# MotorController.net
KiCad netlist of a schematic drawn in EAGLE
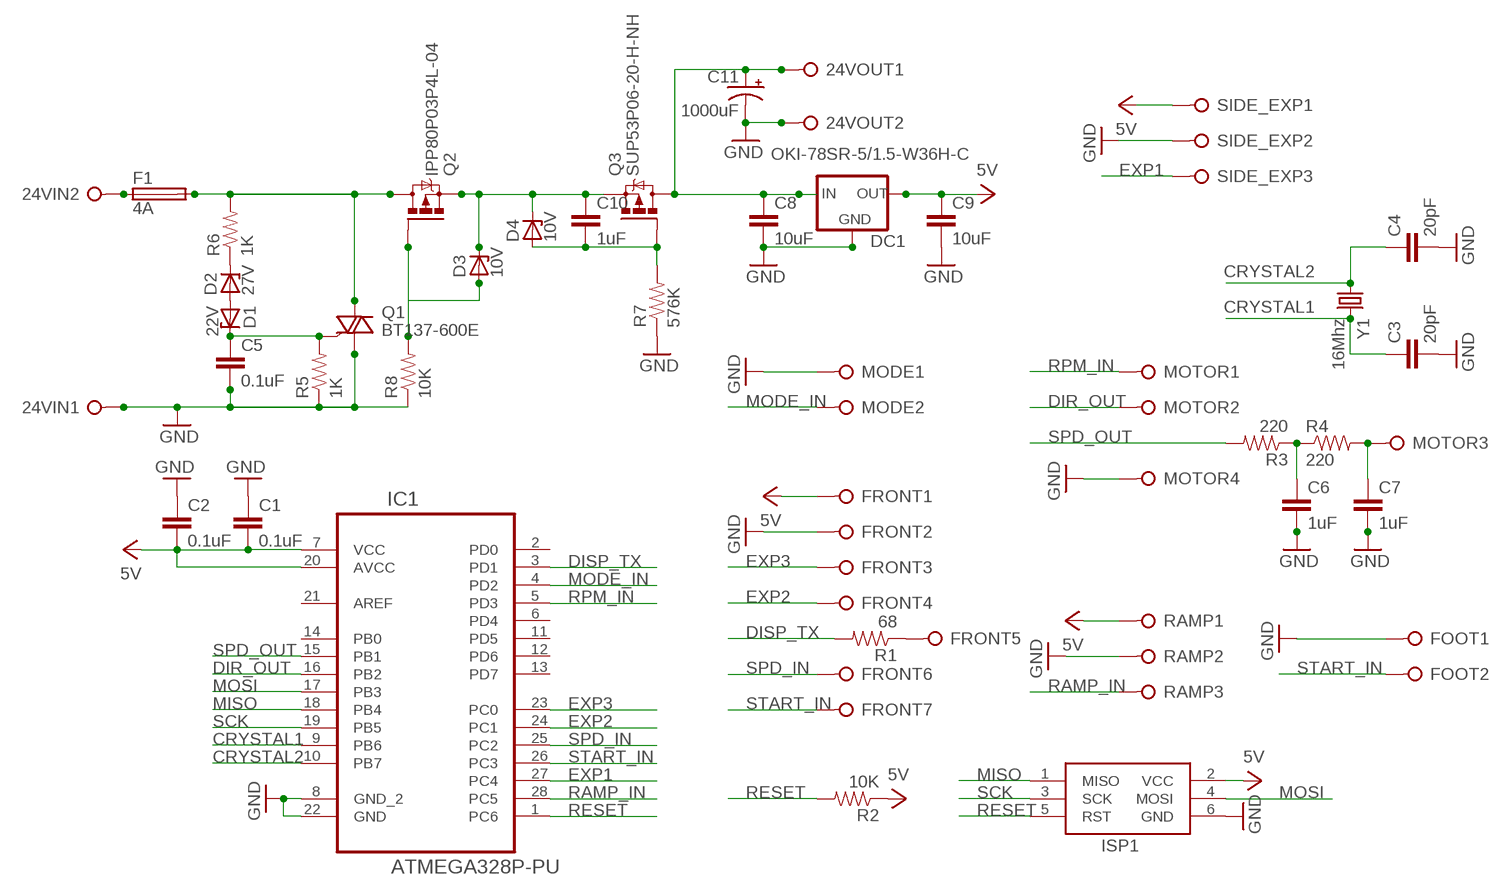
[diagram p0: schematic, sheet 1]

(export (version "E")
  (design (tool "Eeschema 10.0.6"))
  (components
    (comp (ref "24VIN")
      (value "PINHD-1X2BIG")
      (footprint "eagle-import:1X02-BIG")
      (libsource (lib "eagle-import") (part "PINHD-1X2BIG"))
    )
    (comp (ref "24VOUT")
      (value "PINHD-1X2BIG")
      (footprint "eagle-import:1X02-BIG")
      (libsource (lib "eagle-import") (part "PINHD-1X2BIG"))
    )
    (comp (ref "C1")
      (value "0.1uF")
      (footprint "eagle-import:CAPACITOR-2.5MM")
      (libsource (lib "eagle-import") (part "CAPACITOR-2.5MM"))
    )
    (comp (ref "C2")
      (value "0.1uF")
      (footprint "eagle-import:CAPACITOR-2.5MM")
      (libsource (lib "eagle-import") (part "CAPACITOR-2.5MM"))
    )
    (comp (ref "C3")
      (value "20pF")
      (footprint "eagle-import:CAPACITOR-2.5MM")
      (libsource (lib "eagle-import") (part "CAPACITOR-2.5MM"))
    )
    (comp (ref "C4")
      (value "20pF")
      (footprint "eagle-import:CAPACITOR-2.5MM")
      (libsource (lib "eagle-import") (part "CAPACITOR-2.5MM"))
    )
    (comp (ref "C5")
      (value "0.1uF")
      (footprint "eagle-import:CAPACITOR-2.5MM")
      (libsource (lib "eagle-import") (part "CAPACITOR-2.5MM"))
    )
    (comp (ref "C6")
      (value "1uF")
      (footprint "eagle-import:CAPACITOR-2.5MM")
      (libsource (lib "eagle-import") (part "CAPACITOR-2.5MM"))
    )
    (comp (ref "C7")
      (value "1uF")
      (footprint "eagle-import:CAPACITOR-2.5MM")
      (libsource (lib "eagle-import") (part "CAPACITOR-2.5MM"))
    )
    (comp (ref "C8")
      (value "10uF")
      (footprint "eagle-import:CAPACITOR-5MM")
      (libsource (lib "eagle-import") (part "CAPACITOR-5MM"))
    )
    (comp (ref "C9")
      (value "10uF")
      (footprint "eagle-import:CAPACITOR-5MM")
      (libsource (lib "eagle-import") (part "CAPACITOR-5MM"))
    )
    (comp (ref "C10")
      (value "1uF")
      (footprint "eagle-import:CAPACITOR-2.5MM")
      (libsource (lib "eagle-import") (part "CAPACITOR-2.5MM"))
    )
    (comp (ref "C11")
      (value "1000uF")
      (footprint "eagle-import:CAP-POL-25-14")
      (libsource (lib "eagle-import") (part "CAP-POL-25-14"))
    )
    (comp (ref "D1")
      (value "22V")
      (footprint "eagle-import:ZDIO-7.5")
      (libsource (lib "eagle-import") (part "ZENER-7.5"))
    )
    (comp (ref "D2")
      (value "27V")
      (footprint "eagle-import:ZDIO-7.5")
      (libsource (lib "eagle-import") (part "ZENER-7.5"))
    )
    (comp (ref "D3")
      (value "10V")
      (footprint "eagle-import:ZDIO-7.5")
      (libsource (lib "eagle-import") (part "ZENER-7.5"))
    )
    (comp (ref "D4")
      (value "10V")
      (footprint "eagle-import:ZDIO-7.5")
      (libsource (lib "eagle-import") (part "ZENER-7.5"))
    )
    (comp (ref "DC1")
      (value "OKI-78SR-5/1.5-W36H-C")
      (footprint "eagle-import:DC-CONV")
      (libsource (lib "eagle-import") (part "DC-CONV"))
    )
    (comp (ref "F1")
      (value "4A")
      (footprint "eagle-import:FUSE_HOLDER_5X20MM")
      (libsource (lib "eagle-import") (part "FUSE"))
    )
    (comp (ref "FOOT")
      (value "PINHD-1X2BIG")
      (footprint "eagle-import:1X02-BIG")
      (libsource (lib "eagle-import") (part "PINHD-1X2BIG"))
    )
    (comp (ref "FRONT")
      (value "PINHD-1X7BIG")
      (footprint "eagle-import:1X07-BIG")
      (libsource (lib "eagle-import") (part "PINHD-1X7BIG"))
    )
    (comp (ref "IC1")
      (value "ATMEGA328P-PU")
      (footprint "eagle-import:DIP28")
      (libsource (lib "eagle-import") (part "ATMEGA328P-PU"))
    )
    (comp (ref "ISP1")
      (value "ICSP-HEADER-6")
      (footprint "eagle-import:ICSP-HEADER")
      (libsource (lib "eagle-import") (part "ICSP-HEADER-6"))
    )
    (comp (ref "MODE")
      (value "PINHD-1X2BIG")
      (footprint "eagle-import:1X02-BIG")
      (libsource (lib "eagle-import") (part "PINHD-1X2BIG"))
    )
    (comp (ref "MOTOR")
      (value "PINHD-1X4BIG")
      (footprint "eagle-import:1X04-BIG")
      (libsource (lib "eagle-import") (part "PINHD-1X4BIG"))
    )
    (comp (ref "Q1")
      (value "BT137-600E")
      (footprint "eagle-import:TO220BH-NO-HOLE")
      (libsource (lib "eagle-import") (part "TRIAC-H-NH"))
    )
    (comp (ref "Q2")
      (value "IPP80P03P4L-04")
      (footprint "eagle-import:TO220BH-NO-HOLE")
      (libsource (lib "eagle-import") (part "SUP53P06-20-H-NH"))
    )
    (comp (ref "Q3")
      (value "SUP53P06-20-H-NH")
      (footprint "eagle-import:TO220BH-NO-HOLE")
      (libsource (lib "eagle-import") (part "SUP53P06-20-H-NH"))
    )
    (comp (ref "R1")
      (value "68")
      (footprint "eagle-import:AXIAL-7.5MM")
      (libsource (lib "eagle-import") (part "RESISTOR-7.5MM"))
    )
    (comp (ref "R2")
      (value "10K")
      (footprint "eagle-import:AXIAL-7.5MM")
      (libsource (lib "eagle-import") (part "RESISTOR-7.5MM"))
    )
    (comp (ref "R3")
      (value "220")
      (footprint "eagle-import:AXIAL-7.5MM")
      (libsource (lib "eagle-import") (part "RESISTOR-7.5MM"))
    )
    (comp (ref "R4")
      (value "220")
      (footprint "eagle-import:AXIAL-7.5MM")
      (libsource (lib "eagle-import") (part "RESISTOR-7.5MM"))
    )
    (comp (ref "R5")
      (value "1K")
      (footprint "eagle-import:AXIAL-7.5MM")
      (libsource (lib "eagle-import") (part "RESISTOR-7.5MM"))
    )
    (comp (ref "R6")
      (value "1K")
      (footprint "eagle-import:AXIAL-7.5MM")
      (libsource (lib "eagle-import") (part "RESISTOR-7.5MM"))
    )
    (comp (ref "R7")
      (value "576K")
      (footprint "eagle-import:AXIAL-7.5MM")
      (libsource (lib "eagle-import") (part "RESISTOR-7.5MM"))
    )
    (comp (ref "R8")
      (value "10K")
      (footprint "eagle-import:AXIAL-7.5MM")
      (libsource (lib "eagle-import") (part "RESISTOR-7.5MM"))
    )
    (comp (ref "RAMP")
      (value "PINHD-1X3BIG")
      (footprint "eagle-import:1X03-BIG")
      (libsource (lib "eagle-import") (part "PINHD-1X3BIG"))
    )
    (comp (ref "SIDE_EXP")
      (value "PINHD-1X3BIG")
      (footprint "eagle-import:1X03-BIG")
      (libsource (lib "eagle-import") (part "PINHD-1X3BIG"))
    )
    (comp (ref "Y1")
      (value "16Mhz")
      (footprint "eagle-import:CRYSTAL-V")
      (libsource (lib "eagle-import") (part "CRYSTAL-V"))
    )
  )
  (nets
    (net (code "1") (name "/CRYSTAL1") (class "Default")
      (node (ref "C3") (pin "1") (pinfunction "1_1") (pintype "passive"))
      (node (ref "IC1") (pin "9") (pinfunction "PB6_9") (pintype "bidirectional"))
      (node (ref "Y1") (pin "2") (pinfunction "2_2") (pintype "passive"))
    )
    (net (code "2") (name "/CRYSTAL2") (class "Default")
      (node (ref "C4") (pin "1") (pinfunction "1_1") (pintype "passive"))
      (node (ref "IC1") (pin "10") (pinfunction "PB7_10") (pintype "bidirectional"))
      (node (ref "Y1") (pin "1") (pinfunction "1_1") (pintype "passive"))
    )
    (net (code "3") (name "/DIR_OUT") (class "Default")
      (node (ref "IC1") (pin "16") (pinfunction "PB2_16") (pintype "bidirectional"))
      (node (ref "MOTOR") (pin "2") (pinfunction "KL_2") (pintype "passive"))
    )
    (net (code "4") (name "/DISP_TX") (class "Default")
      (node (ref "IC1") (pin "3") (pinfunction "PD1_3") (pintype "bidirectional"))
      (node (ref "R1") (pin "P$2") (pinfunction "2_P$2") (pintype "passive"))
    )
    (net (code "5") (name "/EXP1") (class "Default")
      (node (ref "IC1") (pin "27") (pinfunction "PC4_27") (pintype "bidirectional"))
      (node (ref "SIDE_EXP") (pin "3") (pinfunction "KL_3") (pintype "passive"))
    )
    (net (code "6") (name "/EXP2") (class "Default")
      (node (ref "FRONT") (pin "4") (pinfunction "KL_4") (pintype "passive"))
      (node (ref "IC1") (pin "24") (pinfunction "PC1_24") (pintype "bidirectional"))
    )
    (net (code "7") (name "/EXP3") (class "Default")
      (node (ref "FRONT") (pin "3") (pinfunction "KL_3") (pintype "passive"))
      (node (ref "IC1") (pin "23") (pinfunction "PC0_23") (pintype "bidirectional"))
    )
    (net (code "8") (name "/MISO") (class "Default")
      (node (ref "IC1") (pin "18") (pinfunction "PB4_18") (pintype "bidirectional"))
      (node (ref "ISP1") (pin "1") (pinfunction "MISO_1") (pintype "input"))
    )
    (net (code "9") (name "/MODE_IN") (class "Default")
      (node (ref "IC1") (pin "4") (pinfunction "PD2_4") (pintype "bidirectional"))
      (node (ref "MODE") (pin "2") (pinfunction "KL_2") (pintype "passive"))
    )
    (net (code "10") (name "/MOSI") (class "Default")
      (node (ref "IC1") (pin "17") (pinfunction "PB3_17") (pintype "bidirectional"))
      (node (ref "ISP1") (pin "4") (pinfunction "MOSI_4") (pintype "output"))
    )
    (net (code "11") (name "/RAMP_IN") (class "Default")
      (node (ref "IC1") (pin "28") (pinfunction "PC5_28") (pintype "bidirectional"))
      (node (ref "RAMP") (pin "3") (pinfunction "KL_3") (pintype "passive"))
    )
    (net (code "12") (name "/RESET") (class "Default")
      (node (ref "IC1") (pin "1") (pinfunction "PC6_1") (pintype "bidirectional"))
      (node (ref "ISP1") (pin "5") (pinfunction "RST_5") (pintype "output"))
      (node (ref "R2") (pin "P$2") (pinfunction "2_P$2") (pintype "passive"))
    )
    (net (code "13") (name "/RPM_IN") (class "Default")
      (node (ref "IC1") (pin "5") (pinfunction "PD3_5") (pintype "bidirectional"))
      (node (ref "MOTOR") (pin "1") (pinfunction "KL_1") (pintype "passive"))
    )
    (net (code "14") (name "/SCK") (class "Default")
      (node (ref "IC1") (pin "19") (pinfunction "PB5_19") (pintype "bidirectional"))
      (node (ref "ISP1") (pin "3") (pinfunction "SCK_3") (pintype "output"))
    )
    (net (code "15") (name "/SPD_IN") (class "Default")
      (node (ref "FRONT") (pin "6") (pinfunction "KL_6") (pintype "passive"))
      (node (ref "IC1") (pin "25") (pinfunction "PC2_25") (pintype "bidirectional"))
    )
    (net (code "16") (name "/SPD_OUT") (class "Default")
      (node (ref "IC1") (pin "15") (pinfunction "PB1_15") (pintype "bidirectional"))
      (node (ref "R3") (pin "P$2") (pinfunction "2_P$2") (pintype "passive"))
    )
    (net (code "17") (name "/START_IN") (class "Default")
      (node (ref "FOOT") (pin "2") (pinfunction "KL_2") (pintype "passive"))
      (node (ref "FRONT") (pin "7") (pinfunction "KL_7") (pintype "passive"))
      (node (ref "IC1") (pin "26") (pinfunction "PC3_26") (pintype "bidirectional"))
    )
    (net (code "18") (name "5V") (class "Default")
      (node (ref "C1") (pin "2") (pinfunction "2_2") (pintype "passive"))
      (node (ref "C2") (pin "2") (pinfunction "2_2") (pintype "passive"))
      (node (ref "C9") (pin "1") (pinfunction "1_1") (pintype "passive"))
      (node (ref "DC1") (pin "P3") (pinfunction "OUT_P3") (pintype "passive"))
      (node (ref "FRONT") (pin "1") (pinfunction "KL_1") (pintype "passive"))
      (node (ref "IC1") (pin "20") (pinfunction "AVCC_20") (pintype "power_in"))
      (node (ref "IC1") (pin "7") (pinfunction "VCC_7") (pintype "power_in"))
      (node (ref "ISP1") (pin "2") (pinfunction "VCC_2") (pintype "power_in"))
      (node (ref "R2") (pin "P$1") (pinfunction "1_P$1") (pintype "passive"))
      (node (ref "RAMP") (pin "1") (pinfunction "KL_1") (pintype "passive"))
      (node (ref "SIDE_EXP") (pin "1") (pinfunction "KL_1") (pintype "passive"))
    )
    (net (code "19") (name "GND") (class "Default")
      (node (ref "24VIN") (pin "1") (pinfunction "KL_1") (pintype "passive"))
      (node (ref "24VOUT") (pin "2") (pinfunction "KL_2") (pintype "passive"))
      (node (ref "C1") (pin "1") (pinfunction "1_1") (pintype "passive"))
      (node (ref "C11") (pin "-") (pinfunction "-_-") (pintype "passive"))
      (node (ref "C2") (pin "1") (pinfunction "1_1") (pintype "passive"))
      (node (ref "C3") (pin "2") (pinfunction "2_2") (pintype "passive"))
      (node (ref "C4") (pin "2") (pinfunction "2_2") (pintype "passive"))
      (node (ref "C5") (pin "2") (pinfunction "2_2") (pintype "passive"))
      (node (ref "C6") (pin "2") (pinfunction "2_2") (pintype "passive"))
      (node (ref "C7") (pin "2") (pinfunction "2_2") (pintype "passive"))
      (node (ref "C8") (pin "2") (pinfunction "2_2") (pintype "passive"))
      (node (ref "C9") (pin "2") (pinfunction "2_2") (pintype "passive"))
      (node (ref "DC1") (pin "P2") (pinfunction "GND_P2") (pintype "input"))
      (node (ref "FOOT") (pin "1") (pinfunction "KL_1") (pintype "passive"))
      (node (ref "FRONT") (pin "2") (pinfunction "KL_2") (pintype "passive"))
      (node (ref "IC1") (pin "22") (pinfunction "GND_22") (pintype "passive"))
      (node (ref "IC1") (pin "8") (pinfunction "GND_2_8") (pintype "passive"))
      (node (ref "ISP1") (pin "6") (pinfunction "GND_6") (pintype "power_in"))
      (node (ref "MODE") (pin "1") (pinfunction "KL_1") (pintype "passive"))
      (node (ref "MOTOR") (pin "4") (pinfunction "KL_4") (pintype "passive"))
      (node (ref "Q1") (pin "P1") (pinfunction "A1_P1") (pintype "passive"))
      (node (ref "R5") (pin "P$1") (pinfunction "1_P$1") (pintype "passive"))
      (node (ref "R7") (pin "P$1") (pinfunction "1_P$1") (pintype "passive"))
      (node (ref "R8") (pin "P$1") (pinfunction "1_P$1") (pintype "passive"))
      (node (ref "RAMP") (pin "2") (pinfunction "KL_2") (pintype "passive"))
      (node (ref "SIDE_EXP") (pin "2") (pinfunction "KL_2") (pintype "passive"))
    )
    (net (code "20") (name "Net-(24VINB-KL)") (class "Default")
      (node (ref "24VIN") (pin "2") (pinfunction "KL_2") (pintype "passive"))
      (node (ref "F1") (pin "1") (pinfunction "1_1") (pintype "passive"))
    )
    (net (code "21") (name "Net-(24VOUTA-KL)") (class "Default")
      (node (ref "24VOUT") (pin "1") (pinfunction "KL_1") (pintype "passive"))
      (node (ref "C11") (pin "+") (pinfunction "+_+") (pintype "passive"))
      (node (ref "C8") (pin "1") (pinfunction "1_1") (pintype "passive"))
      (node (ref "DC1") (pin "P1") (pinfunction "IN_P1") (pintype "input"))
      (node (ref "Q3") (pin "P2") (pinfunction "D_P2") (pintype "passive"))
    )
    (net (code "22") (name "Net-(D1-PadA)") (class "Default")
      (node (ref "D1") (pin "A") (pinfunction "A_A") (pintype "passive"))
      (node (ref "D2") (pin "A") (pinfunction "A_A") (pintype "passive"))
    )
    (net (code "23") (name "Net-(FRONTE-KL)") (class "Default")
      (node (ref "FRONT") (pin "5") (pinfunction "KL_5") (pintype "passive"))
      (node (ref "R1") (pin "P$1") (pinfunction "1_P$1") (pintype "passive"))
    )
    (net (code "24") (name "Net-(MOTORC-KL)") (class "Default")
      (node (ref "C7") (pin "1") (pinfunction "1_1") (pintype "passive"))
      (node (ref "MOTOR") (pin "3") (pinfunction "KL_3") (pintype "passive"))
      (node (ref "R4") (pin "P$2") (pinfunction "2_P$2") (pintype "passive"))
    )
    (net (code "25") (name "Net-(Q1-A2)") (class "Default")
      (node (ref "F1") (pin "2") (pinfunction "2_2") (pintype "passive"))
      (node (ref "Q1") (pin "P2") (pinfunction "A2_P2") (pintype "passive"))
      (node (ref "Q2") (pin "P2") (pinfunction "D_P2") (pintype "passive"))
      (node (ref "R6") (pin "P$2") (pinfunction "2_P$2") (pintype "passive"))
    )
    (net (code "26") (name "Net-(Q1-G)") (class "Default")
      (node (ref "C5") (pin "1") (pinfunction "1_1") (pintype "passive"))
      (node (ref "D1") (pin "C") (pinfunction "C_C") (pintype "passive"))
      (node (ref "Q1") (pin "P3") (pinfunction "G_P3") (pintype "passive"))
      (node (ref "R5") (pin "P$2") (pinfunction "2_P$2") (pintype "passive"))
    )
    (net (code "27") (name "Net-(Q2-G)") (class "Default")
      (node (ref "D3") (pin "A") (pinfunction "A_A") (pintype "passive"))
      (node (ref "Q2") (pin "P1") (pinfunction "G_P1") (pintype "passive"))
      (node (ref "R8") (pin "P$2") (pinfunction "2_P$2") (pintype "passive"))
    )
    (net (code "28") (name "Net-(Q2-S)") (class "Default")
      (node (ref "C10") (pin "1") (pinfunction "1_1") (pintype "passive"))
      (node (ref "D3") (pin "C") (pinfunction "C_C") (pintype "passive"))
      (node (ref "D4") (pin "C") (pinfunction "C_C") (pintype "passive"))
      (node (ref "Q2") (pin "P3") (pinfunction "S_P3") (pintype "passive"))
      (node (ref "Q3") (pin "P3") (pinfunction "S_P3") (pintype "passive"))
    )
    (net (code "29") (name "Net-(Q3-G)") (class "Default")
      (node (ref "C10") (pin "2") (pinfunction "2_2") (pintype "passive"))
      (node (ref "D4") (pin "A") (pinfunction "A_A") (pintype "passive"))
      (node (ref "Q3") (pin "P1") (pinfunction "G_P1") (pintype "passive"))
      (node (ref "R7") (pin "P$2") (pinfunction "2_P$2") (pintype "passive"))
    )
    (net (code "30") (name "Net-(R3-1)") (class "Default")
      (node (ref "C6") (pin "1") (pinfunction "1_1") (pintype "passive"))
      (node (ref "R3") (pin "P$1") (pinfunction "1_P$1") (pintype "passive"))
      (node (ref "R4") (pin "P$1") (pinfunction "1_P$1") (pintype "passive"))
    )
    (net (code "31") (name "Net-(R6-1)") (class "Default")
      (node (ref "D2") (pin "C") (pinfunction "C_C") (pintype "passive"))
      (node (ref "R6") (pin "P$1") (pinfunction "1_P$1") (pintype "passive"))
    )
    (net (code "32") (name "unconnected-(IC1-AREF-Pad21)") (class "Default")
      (node (ref "IC1") (pin "21") (pinfunction "AREF_21") (pintype "input"))
    )
    (net (code "33") (name "unconnected-(IC1-PB0-Pad14)") (class "Default")
      (node (ref "IC1") (pin "14") (pinfunction "PB0_14") (pintype "bidirectional"))
    )
    (net (code "34") (name "unconnected-(IC1-PD0-Pad2)") (class "Default")
      (node (ref "IC1") (pin "2") (pinfunction "PD0_2") (pintype "bidirectional"))
    )
    (net (code "35") (name "unconnected-(IC1-PD4-Pad6)") (class "Default")
      (node (ref "IC1") (pin "6") (pinfunction "PD4_6") (pintype "bidirectional"))
    )
    (net (code "36") (name "unconnected-(IC1-PD5-Pad11)") (class "Default")
      (node (ref "IC1") (pin "11") (pinfunction "PD5_11") (pintype "bidirectional"))
    )
    (net (code "37") (name "unconnected-(IC1-PD6-Pad12)") (class "Default")
      (node (ref "IC1") (pin "12") (pinfunction "PD6_12") (pintype "bidirectional"))
    )
    (net (code "38") (name "unconnected-(IC1-PD7-Pad13)") (class "Default")
      (node (ref "IC1") (pin "13") (pinfunction "PD7_13") (pintype "bidirectional"))
    )
  )
)
